# irrigator.net
KiCad netlist of a schematic drawn in EAGLE
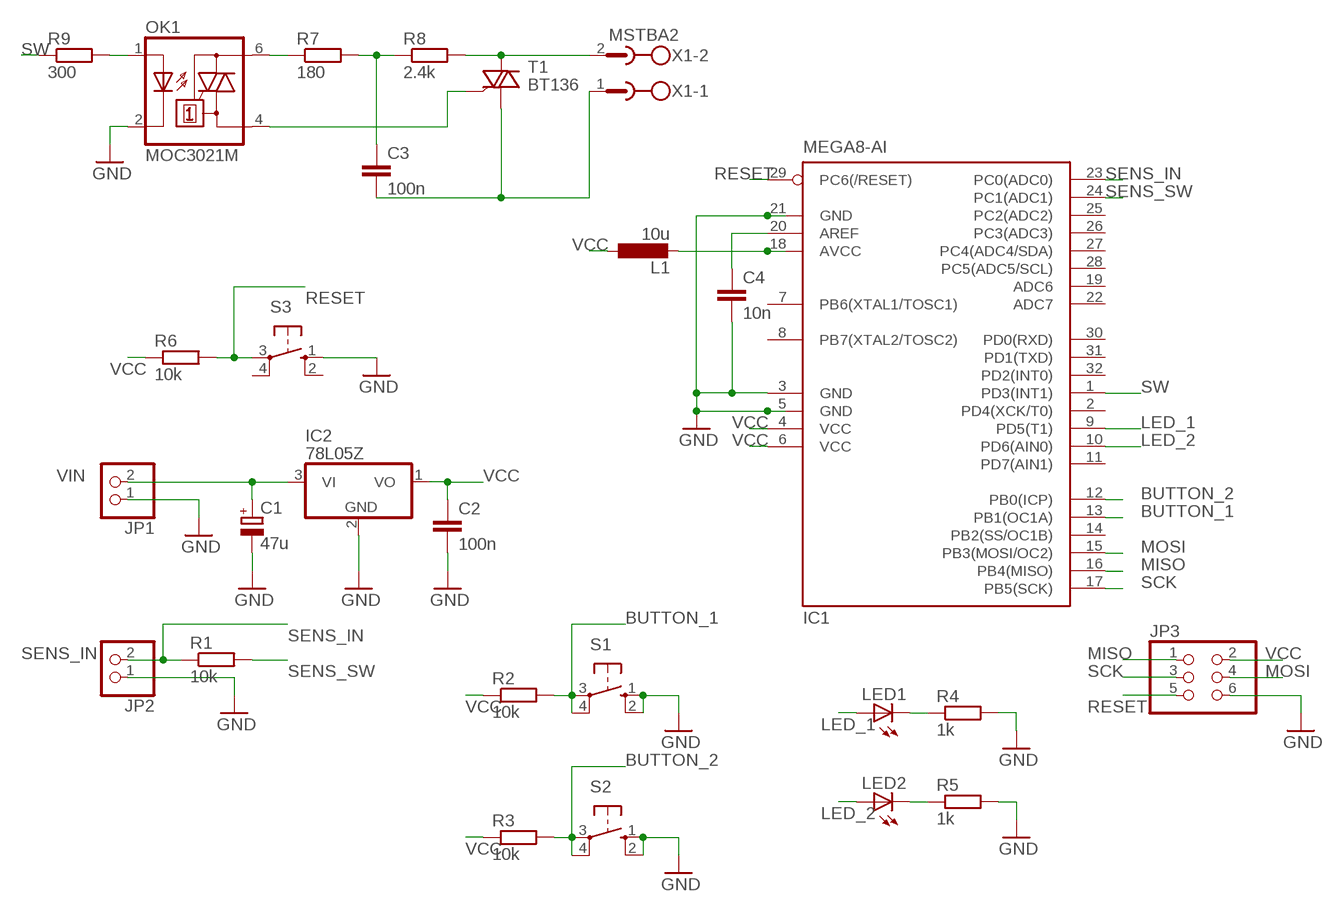
[diagram p0: schematic, sheet 1]

(export (version "E")
  (design (tool "Eeschema 10.0.6"))
  (components
    (comp (ref "C1")
      (value "47u")
      (footprint "eagle-import:E2,5-6E")
      (libsource (lib "eagle-import") (part "CPOL-EUE2,5-6E"))
    )
    (comp (ref "C2")
      (value "100n")
      (footprint "eagle-import:C1206")
      (libsource (lib "eagle-import") (part "C-EUC1206"))
    )
    (comp (ref "C3")
      (value "100n")
      (footprint "eagle-import:C1206")
      (libsource (lib "eagle-import") (part "C-EUC1206"))
    )
    (comp (ref "C4")
      (value "10n")
      (footprint "eagle-import:C1206")
      (libsource (lib "eagle-import") (part "C-EUC1206"))
    )
    (comp (ref "IC1")
      (value "MEGA8-AI")
      (footprint "eagle-import:TQFP32-08")
      (fields (field (name "MPN") "ATMEGA8-16AU"))
      (libsource (lib "eagle-import") (part "MEGA8-AI"))
    )
    (comp (ref "IC2")
      (value "78L05Z")
      (footprint "eagle-import:TO92")
      (libsource (lib "eagle-import") (part "78ZL05"))
    )
    (comp (ref "JP1")
      (value "PINHD-1X2")
      (footprint "eagle-import:1X02")
      (libsource (lib "eagle-import") (part "PINHD-1X2"))
    )
    (comp (ref "JP2")
      (value "PINHD-1X2")
      (footprint "eagle-import:1X02")
      (libsource (lib "eagle-import") (part "PINHD-1X2"))
    )
    (comp (ref "JP3")
      (value "PINHD-2X3")
      (footprint "eagle-import:2X03")
      (libsource (lib "eagle-import") (part "PINHD-2X3"))
    )
    (comp (ref "L1")
      (value "10u")
      (footprint "eagle-import:L3216C")
      (libsource (lib "eagle-import") (part "L-EUL3216C"))
    )
    (comp (ref "LED1")
      (value "LED5MM")
      (footprint "eagle-import:LED5MM")
      (libsource (lib "eagle-import") (part "LED5MM"))
    )
    (comp (ref "LED2")
      (value "LED5MM")
      (footprint "eagle-import:LED5MM")
      (libsource (lib "eagle-import") (part "LED5MM"))
    )
    (comp (ref "OK1")
      (value "MOC3021M")
      (footprint "eagle-import:DIL06")
      (fields (field (name "MF") "FAIRCHILD SEMICONDUCTOR") (field (name "MPN") "MOC3021-M"))
      (libsource (lib "eagle-import") (part "MOC30M21"))
    )
    (comp (ref "R1")
      (value "10k")
      (footprint "eagle-import:R1206")
      (libsource (lib "eagle-import") (part "R-EU_R1206"))
    )
    (comp (ref "R2")
      (value "10k")
      (footprint "eagle-import:R1206")
      (libsource (lib "eagle-import") (part "R-EU_R1206"))
    )
    (comp (ref "R3")
      (value "10k")
      (footprint "eagle-import:R1206")
      (libsource (lib "eagle-import") (part "R-EU_R1206"))
    )
    (comp (ref "R4")
      (value "1k")
      (footprint "eagle-import:R1206")
      (libsource (lib "eagle-import") (part "R-EU_R1206"))
    )
    (comp (ref "R5")
      (value "1k")
      (footprint "eagle-import:R1206")
      (libsource (lib "eagle-import") (part "R-EU_R1206"))
    )
    (comp (ref "R6")
      (value "10k")
      (footprint "eagle-import:R1206")
      (libsource (lib "eagle-import") (part "R-EU_R1206"))
    )
    (comp (ref "R7")
      (value "180")
      (footprint "eagle-import:R1206")
      (libsource (lib "eagle-import") (part "R-EU_R1206"))
    )
    (comp (ref "R8")
      (value "2.4k")
      (footprint "eagle-import:R1206")
      (libsource (lib "eagle-import") (part "R-EU_R1206"))
    )
    (comp (ref "R9")
      (value "300")
      (footprint "eagle-import:R1206")
      (libsource (lib "eagle-import") (part "R-EU_R1206"))
    )
    (comp (ref "S1")
      (value "10-XX")
      (footprint "eagle-import:B3F-10XX")
      (fields (field (name "MPN") "B3F-1000"))
      (libsource (lib "eagle-import") (part "10-XX"))
    )
    (comp (ref "S2")
      (value "10-XX")
      (footprint "eagle-import:B3F-10XX")
      (fields (field (name "MPN") "B3F-1000"))
      (libsource (lib "eagle-import") (part "10-XX"))
    )
    (comp (ref "S3")
      (value "10-XX")
      (footprint "eagle-import:B3F-10XX")
      (fields (field (name "MPN") "B3F-1000"))
      (libsource (lib "eagle-import") (part "10-XX"))
    )
    (comp (ref "T1")
      (value "BT136")
      (footprint "eagle-import:TO220AB")
      (libsource (lib "eagle-import") (part "BT136"))
    )
    (comp (ref "X1")
      (value "MSTBA2")
      (footprint "eagle-import:MSTBA2")
      (fields (field (name "MF") "FARNELL") (field (name "MPN") "1757242"))
      (libsource (lib "eagle-import") (part "MSTBA2"))
    )
  )
  (nets
    (net (code "1") (name "/BUTTON_1") (class "Default")
      (node (ref "IC1") (pin "13") (pinfunction "PB1(OC1A)_13") (pintype "bidirectional"))
      (node (ref "R2") (pin "2") (pinfunction "2_2") (pintype "passive"))
      (node (ref "S1") (pin "3") (pinfunction "P_3") (pintype "passive"))
      (node (ref "S1") (pin "4") (pinfunction "P1_4") (pintype "passive"))
    )
    (net (code "2") (name "/BUTTON_2") (class "Default")
      (node (ref "IC1") (pin "12") (pinfunction "PB0(ICP)_12") (pintype "bidirectional"))
      (node (ref "R3") (pin "2") (pinfunction "2_2") (pintype "passive"))
      (node (ref "S2") (pin "3") (pinfunction "P_3") (pintype "passive"))
      (node (ref "S2") (pin "4") (pinfunction "P1_4") (pintype "passive"))
    )
    (net (code "3") (name "/LED_1") (class "Default")
      (node (ref "IC1") (pin "9") (pinfunction "PD5(T1)_9") (pintype "bidirectional"))
      (node (ref "LED1") (pin "A") (pinfunction "A_A") (pintype "passive"))
    )
    (net (code "4") (name "/LED_2") (class "Default")
      (node (ref "IC1") (pin "10") (pinfunction "PD6(AIN0)_10") (pintype "bidirectional"))
      (node (ref "LED2") (pin "A") (pinfunction "A_A") (pintype "passive"))
    )
    (net (code "5") (name "/MISO") (class "Default")
      (node (ref "IC1") (pin "16") (pinfunction "PB4(MISO)_16") (pintype "bidirectional"))
      (node (ref "JP3") (pin "1") (pinfunction "1_1") (pintype "passive"))
    )
    (net (code "6") (name "/MOSI") (class "Default")
      (node (ref "IC1") (pin "15") (pinfunction "PB3(MOSI/OC2)_15") (pintype "bidirectional"))
      (node (ref "JP3") (pin "4") (pinfunction "4_4") (pintype "passive"))
    )
    (net (code "7") (name "/RESET") (class "Default")
      (node (ref "IC1") (pin "29") (pinfunction "PC6(/RESET)_29") (pintype "bidirectional"))
      (node (ref "JP3") (pin "5") (pinfunction "5_5") (pintype "passive"))
      (node (ref "R6") (pin "2") (pinfunction "2_2") (pintype "passive"))
      (node (ref "S3") (pin "3") (pinfunction "P_3") (pintype "passive"))
    )
    (net (code "8") (name "/SCK") (class "Default")
      (node (ref "IC1") (pin "17") (pinfunction "PB5(SCK)_17") (pintype "bidirectional"))
      (node (ref "JP3") (pin "3") (pinfunction "3_3") (pintype "passive"))
    )
    (net (code "9") (name "/SENS_IN") (class "Default")
      (node (ref "IC1") (pin "23") (pinfunction "PC0(ADC0)_23") (pintype "bidirectional"))
      (node (ref "JP2") (pin "2") (pinfunction "2_2") (pintype "passive"))
      (node (ref "R1") (pin "1") (pinfunction "1_1") (pintype "passive"))
    )
    (net (code "10") (name "/SENS_SW") (class "Default")
      (node (ref "IC1") (pin "24") (pinfunction "PC1(ADC1)_24") (pintype "bidirectional"))
      (node (ref "R1") (pin "2") (pinfunction "2_2") (pintype "passive"))
    )
    (net (code "11") (name "/SW") (class "Default")
      (node (ref "IC1") (pin "1") (pinfunction "PD3(INT1)_1") (pintype "bidirectional"))
      (node (ref "R9") (pin "1") (pinfunction "1_1") (pintype "passive"))
    )
    (net (code "12") (name "/VCC") (class "Default")
      (node (ref "C2") (pin "1") (pinfunction "1_1") (pintype "passive"))
      (node (ref "IC1") (pin "4") (pinfunction "VCC_4") (pintype "power_in"))
      (node (ref "IC1") (pin "6") (pinfunction "VCC_6") (pintype "power_in"))
      (node (ref "IC2") (pin "1") (pinfunction "VO_1") (pintype "passive"))
      (node (ref "JP3") (pin "2") (pinfunction "2_2") (pintype "passive"))
      (node (ref "L1") (pin "1") (pinfunction "1_1") (pintype "passive"))
      (node (ref "R2") (pin "1") (pinfunction "1_1") (pintype "passive"))
      (node (ref "R3") (pin "1") (pinfunction "1_1") (pintype "passive"))
      (node (ref "R6") (pin "1") (pinfunction "1_1") (pintype "passive"))
    )
    (net (code "13") (name "/VIN") (class "Default")
      (node (ref "C1") (pin "+") (pinfunction "+_+") (pintype "passive"))
      (node (ref "IC2") (pin "3") (pinfunction "VI_3") (pintype "input"))
      (node (ref "JP1") (pin "2") (pinfunction "2_2") (pintype "passive"))
    )
    (net (code "14") (name "GND") (class "Default")
      (node (ref "C1") (pin "-") (pinfunction "-_-") (pintype "passive"))
      (node (ref "C2") (pin "2") (pinfunction "2_2") (pintype "passive"))
      (node (ref "C4") (pin "2") (pinfunction "2_2") (pintype "passive"))
      (node (ref "IC1") (pin "21") (pinfunction "GND_21") (pintype "power_in"))
      (node (ref "IC1") (pin "3") (pinfunction "GND_3") (pintype "power_in"))
      (node (ref "IC1") (pin "5") (pinfunction "GND_5") (pintype "power_in"))
      (node (ref "IC2") (pin "2") (pinfunction "GND_2") (pintype "passive"))
      (node (ref "JP1") (pin "1") (pinfunction "1_1") (pintype "passive"))
      (node (ref "JP2") (pin "1") (pinfunction "1_1") (pintype "passive"))
      (node (ref "JP3") (pin "6") (pinfunction "6_6") (pintype "passive"))
      (node (ref "OK1") (pin "2") (pinfunction "C_2") (pintype "passive"))
      (node (ref "R4") (pin "2") (pinfunction "2_2") (pintype "passive"))
      (node (ref "R5") (pin "2") (pinfunction "2_2") (pintype "passive"))
      (node (ref "S1") (pin "1") (pinfunction "S_1") (pintype "passive"))
      (node (ref "S1") (pin "2") (pinfunction "S1_2") (pintype "passive"))
      (node (ref "S2") (pin "1") (pinfunction "S_1") (pintype "passive"))
      (node (ref "S2") (pin "2") (pinfunction "S1_2") (pintype "passive"))
      (node (ref "S3") (pin "1") (pinfunction "S_1") (pintype "passive"))
    )
    (net (code "15") (name "Net-(C3-Pad1)") (class "Default")
      (node (ref "C3") (pin "1") (pinfunction "1_1") (pintype "passive"))
      (node (ref "R7") (pin "2") (pinfunction "2_2") (pintype "passive"))
      (node (ref "R8") (pin "1") (pinfunction "1_1") (pintype "passive"))
    )
    (net (code "16") (name "Net-(IC1-AREF)") (class "Default")
      (node (ref "C4") (pin "1") (pinfunction "1_1") (pintype "passive"))
      (node (ref "IC1") (pin "20") (pinfunction "AREF_20") (pintype "passive"))
    )
    (net (code "17") (name "Net-(IC1-AVCC)") (class "Default")
      (node (ref "IC1") (pin "18") (pinfunction "AVCC_18") (pintype "power_in"))
      (node (ref "L1") (pin "2") (pinfunction "2_2") (pintype "passive"))
    )
    (net (code "18") (name "Net-(LED1-C)") (class "Default")
      (node (ref "LED1") (pin "K") (pinfunction "C_K") (pintype "passive"))
      (node (ref "R4") (pin "1") (pinfunction "1_1") (pintype "passive"))
    )
    (net (code "19") (name "Net-(LED2-C)") (class "Default")
      (node (ref "LED2") (pin "K") (pinfunction "C_K") (pintype "passive"))
      (node (ref "R5") (pin "1") (pinfunction "1_1") (pintype "passive"))
    )
    (net (code "20") (name "Net-(OK1-A)") (class "Default")
      (node (ref "OK1") (pin "1") (pinfunction "A_1") (pintype "passive"))
      (node (ref "R9") (pin "2") (pinfunction "2_2") (pintype "passive"))
    )
    (net (code "21") (name "Net-(OK1-A1)") (class "Default")
      (node (ref "OK1") (pin "4") (pinfunction "A1_4") (pintype "passive"))
      (node (ref "T1") (pin "3") (pinfunction "G_3") (pintype "passive"))
    )
    (net (code "22") (name "Net-(OK1-A2)") (class "Default")
      (node (ref "OK1") (pin "6") (pinfunction "A2_6") (pintype "passive"))
      (node (ref "R7") (pin "1") (pinfunction "1_1") (pintype "passive"))
    )
    (net (code "23") (name "Net-(T1-A1)") (class "Default")
      (node (ref "C3") (pin "2") (pinfunction "2_2") (pintype "passive"))
      (node (ref "T1") (pin "1") (pinfunction "A1_1") (pintype "passive"))
      (node (ref "X1") (pin "1") (pinfunction "1_1") (pintype "passive"))
    )
    (net (code "24") (name "Net-(T1-A2)") (class "Default")
      (node (ref "R8") (pin "2") (pinfunction "2_2") (pintype "passive"))
      (node (ref "T1") (pin "2") (pinfunction "A2_2") (pintype "passive"))
      (node (ref "X1") (pin "2") (pinfunction "1_2") (pintype "passive"))
    )
    (net (code "25") (name "unconnected-(IC1-ADC6-Pad19)") (class "Default")
      (node (ref "IC1") (pin "19") (pinfunction "ADC6_19") (pintype "bidirectional"))
    )
    (net (code "26") (name "unconnected-(IC1-ADC7-Pad22)") (class "Default")
      (node (ref "IC1") (pin "22") (pinfunction "ADC7_22") (pintype "bidirectional"))
    )
    (net (code "27") (name "unconnected-(IC1-PB2(SS{slash}OC1B)-Pad14)") (class "Default")
      (node (ref "IC1") (pin "14") (pinfunction "PB2(SS/OC1B)_14") (pintype "bidirectional"))
    )
    (net (code "28") (name "unconnected-(IC1-PB6(XTAL1{slash}TOSC1)-Pad7)") (class "Default")
      (node (ref "IC1") (pin "7") (pinfunction "PB6(XTAL1/TOSC1)_7") (pintype "bidirectional"))
    )
    (net (code "29") (name "unconnected-(IC1-PB7(XTAL2{slash}TOSC2)-Pad8)") (class "Default")
      (node (ref "IC1") (pin "8") (pinfunction "PB7(XTAL2/TOSC2)_8") (pintype "bidirectional"))
    )
    (net (code "30") (name "unconnected-(IC1-PC2(ADC2)-Pad25)") (class "Default")
      (node (ref "IC1") (pin "25") (pinfunction "PC2(ADC2)_25") (pintype "bidirectional"))
    )
    (net (code "31") (name "unconnected-(IC1-PC3(ADC3)-Pad26)") (class "Default")
      (node (ref "IC1") (pin "26") (pinfunction "PC3(ADC3)_26") (pintype "bidirectional"))
    )
    (net (code "32") (name "unconnected-(IC1-PC4(ADC4{slash}SDA)-Pad27)") (class "Default")
      (node (ref "IC1") (pin "27") (pinfunction "PC4(ADC4/SDA)_27") (pintype "bidirectional"))
    )
    (net (code "33") (name "unconnected-(IC1-PC5(ADC5{slash}SCL)-Pad28)") (class "Default")
      (node (ref "IC1") (pin "28") (pinfunction "PC5(ADC5/SCL)_28") (pintype "bidirectional"))
    )
    (net (code "34") (name "unconnected-(IC1-PD0(RXD)-Pad30)") (class "Default")
      (node (ref "IC1") (pin "30") (pinfunction "PD0(RXD)_30") (pintype "bidirectional"))
    )
    (net (code "35") (name "unconnected-(IC1-PD1(TXD)-Pad31)") (class "Default")
      (node (ref "IC1") (pin "31") (pinfunction "PD1(TXD)_31") (pintype "bidirectional"))
    )
    (net (code "36") (name "unconnected-(IC1-PD2(INT0)-Pad32)") (class "Default")
      (node (ref "IC1") (pin "32") (pinfunction "PD2(INT0)_32") (pintype "bidirectional"))
    )
    (net (code "37") (name "unconnected-(IC1-PD4(XCK{slash}T0)-Pad2)") (class "Default")
      (node (ref "IC1") (pin "2") (pinfunction "PD4(XCK/T0)_2") (pintype "bidirectional"))
    )
    (net (code "38") (name "unconnected-(IC1-PD7(AIN1)-Pad11)") (class "Default")
      (node (ref "IC1") (pin "11") (pinfunction "PD7(AIN1)_11") (pintype "bidirectional"))
    )
    (net (code "39") (name "unconnected-(S3-P1-Pad4)") (class "Default")
      (node (ref "S3") (pin "4") (pinfunction "P1_4") (pintype "passive"))
    )
    (net (code "40") (name "unconnected-(S3-S1-Pad2)") (class "Default")
      (node (ref "S3") (pin "2") (pinfunction "S1_2") (pintype "passive"))
    )
  )
)
